# QSPI.net
KiCad netlist of a schematic drawn in Altium Designer
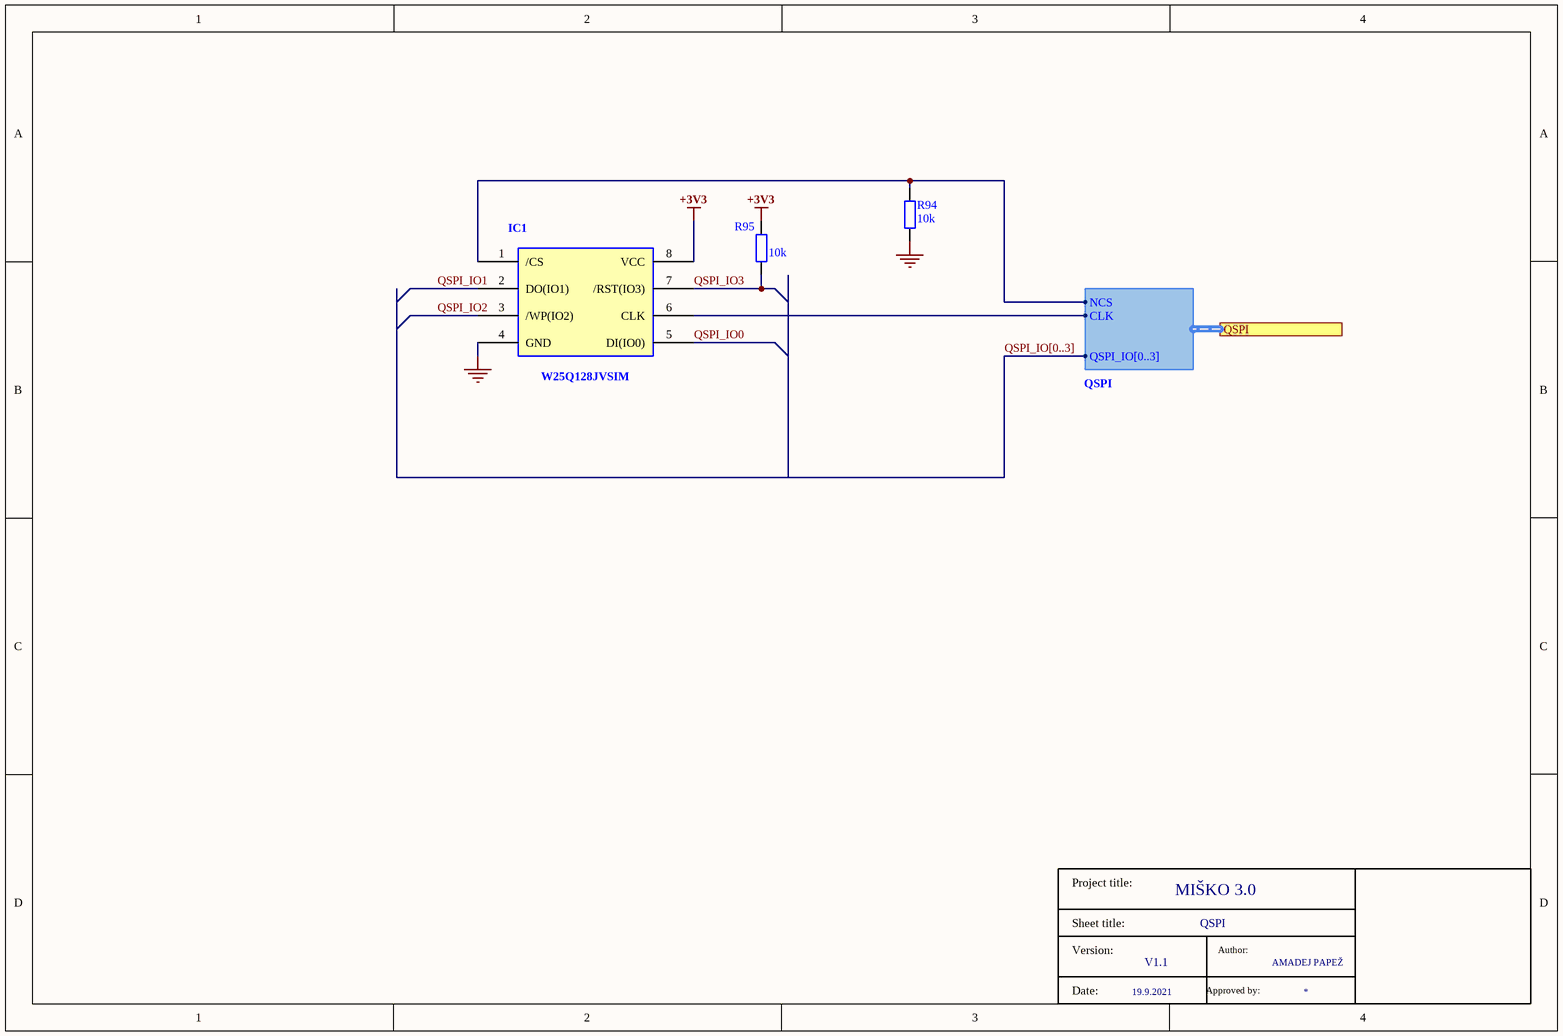
[diagram p0: QSPI.SchDoc]

(export (version "E")
  (design (tool "Eeschema 10.0.6"))
  (components
    (comp (ref "IC1")
      (value "W25Q128JVSIM")
      (footprint "W25Q128JVSIM")
      (description "FLASH - NOR Memory IC 128Mb (16M x 8) SPI - Quad I/O, QPI, DTR 133MHz 8-SOIC")
      (libsource (lib "MISKO3_V6") (part "W25Q128JVSIM"))
    )
    (comp (ref "R94")
      (value "10k")
      (footprint "R1608_0603I_L")
      (description "R")
      (libsource (lib "MISKO3_V6") (part "R"))
    )
    (comp (ref "R95")
      (value "10k")
      (footprint "R1608_0603I_L")
      (description "R")
      (libsource (lib "MISKO3_V6") (part "R"))
    )
    (comp (ref "T12") (value "~") (libsource (lib "MISKO3_V6") (part "Title block")))
  )
  (nets
    (net (code "2") (name "+3V3") (class "Default")
      (node (ref "IC1") (pin "8") (pinfunction "VCC_8") (pintype "passive"))
      (node (ref "R95") (pin "1") (pintype "passive"))
    )
    (net (code "3") (name "/CLK") (class "Default")
      (node (ref "IC1") (pin "6") (pinfunction "CLK_6") (pintype "passive"))
    )
    (net (code "4") (name "/NCS") (class "Default")
      (node (ref "IC1") (pin "1") (pinfunction "/CS_1") (pintype "passive"))
      (node (ref "R94") (pin "1") (pintype "passive"))
    )
    (net (code "5") (name "/QSPI_IO0") (class "Default")
      (node (ref "IC1") (pin "5") (pinfunction "DI(IO0)_5") (pintype "passive"))
    )
    (net (code "6") (name "/QSPI_IO1") (class "Default")
      (node (ref "IC1") (pin "2") (pinfunction "DO(IO1)_2") (pintype "passive"))
    )
    (net (code "7") (name "/QSPI_IO2") (class "Default")
      (node (ref "IC1") (pin "3") (pinfunction "/WP(IO2)_3") (pintype "passive"))
    )
    (net (code "8") (name "/QSPI_IO3") (class "Default")
      (node (ref "IC1") (pin "7") (pinfunction "/RST(IO3)_7") (pintype "passive"))
      (node (ref "R95") (pin "2") (pintype "passive"))
    )
    (net (code "11") (name "GND") (class "Default")
      (node (ref "IC1") (pin "4") (pinfunction "GND_4") (pintype "passive"))
      (node (ref "R94") (pin "2") (pintype "passive"))
    )
  )
)
